# GroundStationCR.net
KiCad netlist of a schematic drawn in EAGLE
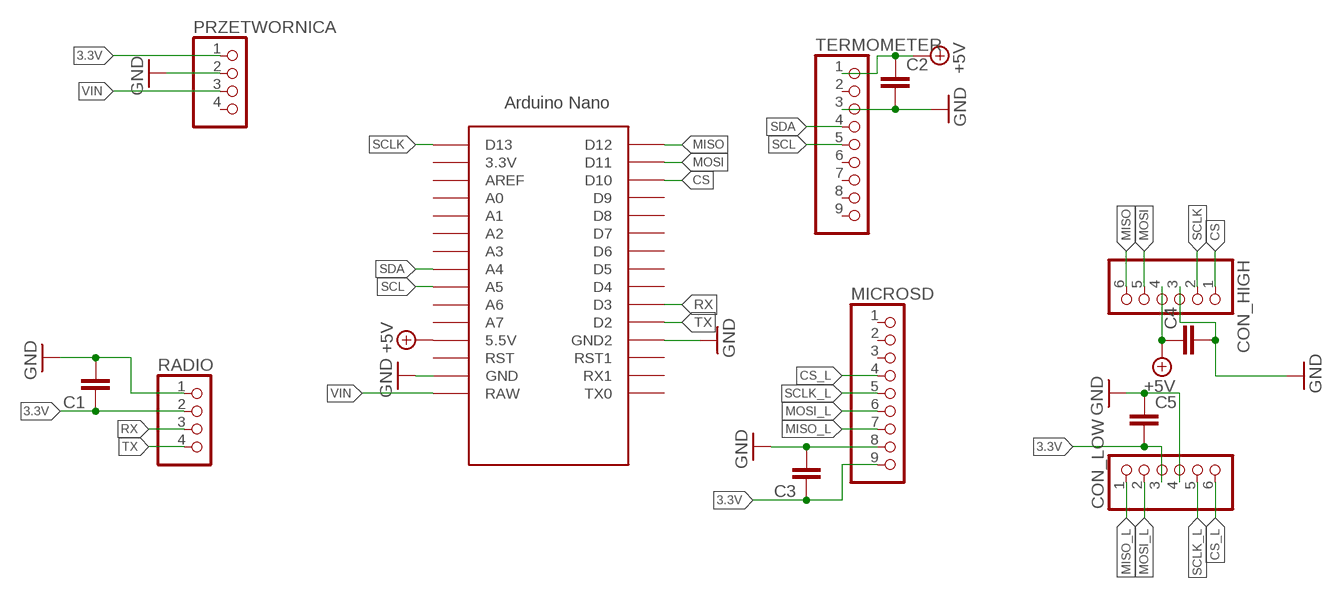
[diagram p0: schematic, sheet 1]

(export (version "E")
  (design (tool "Eeschema 10.0.6"))
  (components
    (comp (ref "C1")
      (value "C-EU050-025X075")
      (footprint "eagle-import:C050-025X075")
      (libsource (lib "eagle-import") (part "C-EU050-025X075"))
    )
    (comp (ref "C2")
      (value "C-EU050-025X075")
      (footprint "eagle-import:C050-025X075")
      (libsource (lib "eagle-import") (part "C-EU050-025X075"))
    )
    (comp (ref "C3")
      (value "C-EU050-025X075")
      (footprint "eagle-import:C050-025X075")
      (libsource (lib "eagle-import") (part "C-EU050-025X075"))
    )
    (comp (ref "C4")
      (value "C-EU050-025X075")
      (footprint "eagle-import:C050-025X075")
      (libsource (lib "eagle-import") (part "C-EU050-025X075"))
    )
    (comp (ref "C5")
      (value "C-EU050-025X075")
      (footprint "eagle-import:C050-025X075")
      (libsource (lib "eagle-import") (part "C-EU050-025X075"))
    )
    (comp (ref "CON_HIGH")
      (value "PINHD-1X6")
      (footprint "eagle-import:1X06")
      (libsource (lib "eagle-import") (part "PINHD-1X6"))
    )
    (comp (ref "CON_LOW")
      (value "PINHD-1X6")
      (footprint "eagle-import:1X06")
      (libsource (lib "eagle-import") (part "PINHD-1X6"))
    )
    (comp (ref "MICROSD")
      (value "PINHD-1X9")
      (footprint "eagle-import:1X09")
      (libsource (lib "eagle-import") (part "PINHD-1X9"))
    )
    (comp (ref "PRZETWORNICA")
      (value "PINHD-1X4")
      (footprint "eagle-import:1X04")
      (libsource (lib "eagle-import") (part "PINHD-1X4"))
    )
    (comp (ref "RADIO")
      (value "PINHD-1X4")
      (footprint "eagle-import:1X04")
      (libsource (lib "eagle-import") (part "PINHD-1X4"))
    )
    (comp (ref "TERMOMETER")
      (value "PINHD-1X9")
      (footprint "eagle-import:1X09")
      (libsource (lib "eagle-import") (part "PINHD-1X9"))
    )
    (comp (ref "U$1")
      (value "NANO")
      (footprint "eagle-import:NANO")
      (libsource (lib "eagle-import") (part "NANO"))
    )
  )
  (nets
    (net (code "1") (name "+5V") (class "Default")
      (node (ref "C2") (pin "1") (pinfunction "1_1") (pintype "passive"))
      (node (ref "C4") (pin "1") (pinfunction "1_1") (pintype "passive"))
      (node (ref "CON_HIGH") (pin "4") (pinfunction "4_4") (pintype "passive"))
      (node (ref "TERMOMETER") (pin "1") (pinfunction "1_1") (pintype "passive"))
      (node (ref "U$1") (pin "5V") (pinfunction "5.5V_5V") (pintype "bidirectional"))
    )
    (net (code "2") (name "3.3V") (class "Default")
      (node (ref "C1") (pin "1") (pinfunction "1_1") (pintype "passive"))
      (node (ref "C3") (pin "1") (pinfunction "1_1") (pintype "passive"))
      (node (ref "C5") (pin "2") (pinfunction "2_2") (pintype "passive"))
      (node (ref "CON_LOW") (pin "3") (pinfunction "3_3") (pintype "passive"))
      (node (ref "MICROSD") (pin "9") (pinfunction "9_9") (pintype "passive"))
      (node (ref "PRZETWORNICA") (pin "1") (pinfunction "1_1") (pintype "passive"))
      (node (ref "RADIO") (pin "2") (pinfunction "2_2") (pintype "passive"))
    )
    (net (code "3") (name "CS") (class "Default")
      (node (ref "CON_HIGH") (pin "1") (pinfunction "1_1") (pintype "passive"))
      (node (ref "U$1") (pin "D10") (pinfunction "D10_D10") (pintype "bidirectional"))
    )
    (net (code "4") (name "CS_L") (class "Default")
      (node (ref "CON_LOW") (pin "6") (pinfunction "6_6") (pintype "passive"))
      (node (ref "MICROSD") (pin "4") (pinfunction "4_4") (pintype "passive"))
    )
    (net (code "5") (name "GND") (class "Default")
      (node (ref "C1") (pin "2") (pinfunction "2_2") (pintype "passive"))
      (node (ref "C2") (pin "2") (pinfunction "2_2") (pintype "passive"))
      (node (ref "C3") (pin "2") (pinfunction "2_2") (pintype "passive"))
      (node (ref "C4") (pin "2") (pinfunction "2_2") (pintype "passive"))
      (node (ref "C5") (pin "1") (pinfunction "1_1") (pintype "passive"))
      (node (ref "CON_HIGH") (pin "3") (pinfunction "3_3") (pintype "passive"))
      (node (ref "CON_LOW") (pin "4") (pinfunction "4_4") (pintype "passive"))
      (node (ref "MICROSD") (pin "8") (pinfunction "8_8") (pintype "passive"))
      (node (ref "PRZETWORNICA") (pin "2") (pinfunction "2_2") (pintype "passive"))
      (node (ref "RADIO") (pin "1") (pinfunction "1_1") (pintype "passive"))
      (node (ref "TERMOMETER") (pin "3") (pinfunction "3_3") (pintype "passive"))
      (node (ref "U$1") (pin "GND") (pinfunction "GND_GND") (pintype "bidirectional"))
      (node (ref "U$1") (pin "GND1") (pinfunction "GND2_GND1") (pintype "bidirectional"))
    )
    (net (code "6") (name "MISO") (class "Default")
      (node (ref "CON_HIGH") (pin "6") (pinfunction "6_6") (pintype "passive"))
      (node (ref "U$1") (pin "D12") (pinfunction "D12_D12") (pintype "bidirectional"))
    )
    (net (code "7") (name "MISO_L") (class "Default")
      (node (ref "CON_LOW") (pin "1") (pinfunction "1_1") (pintype "passive"))
      (node (ref "MICROSD") (pin "7") (pinfunction "7_7") (pintype "passive"))
    )
    (net (code "8") (name "MOSI") (class "Default")
      (node (ref "CON_HIGH") (pin "5") (pinfunction "5_5") (pintype "passive"))
      (node (ref "U$1") (pin "D11") (pinfunction "D11_D11") (pintype "bidirectional"))
    )
    (net (code "9") (name "MOSI_L") (class "Default")
      (node (ref "CON_LOW") (pin "2") (pinfunction "2_2") (pintype "passive"))
      (node (ref "MICROSD") (pin "6") (pinfunction "6_6") (pintype "passive"))
    )
    (net (code "10") (name "RX") (class "Default")
      (node (ref "RADIO") (pin "3") (pinfunction "3_3") (pintype "passive"))
      (node (ref "U$1") (pin "D3") (pinfunction "D3_D3") (pintype "bidirectional"))
    )
    (net (code "11") (name "SCL") (class "Default")
      (node (ref "TERMOMETER") (pin "5") (pinfunction "5_5") (pintype "passive"))
      (node (ref "U$1") (pin "A5") (pinfunction "A5_A5") (pintype "bidirectional"))
    )
    (net (code "12") (name "SCLK") (class "Default")
      (node (ref "CON_HIGH") (pin "2") (pinfunction "2_2") (pintype "passive"))
      (node (ref "U$1") (pin "D13") (pinfunction "D13_D13") (pintype "bidirectional"))
    )
    (net (code "13") (name "SCLK_L") (class "Default")
      (node (ref "CON_LOW") (pin "5") (pinfunction "5_5") (pintype "passive"))
      (node (ref "MICROSD") (pin "5") (pinfunction "5_5") (pintype "passive"))
    )
    (net (code "14") (name "SDA") (class "Default")
      (node (ref "TERMOMETER") (pin "4") (pinfunction "4_4") (pintype "passive"))
      (node (ref "U$1") (pin "A4") (pinfunction "A4_A4") (pintype "bidirectional"))
    )
    (net (code "15") (name "TX") (class "Default")
      (node (ref "RADIO") (pin "4") (pinfunction "4_4") (pintype "passive"))
      (node (ref "U$1") (pin "D2") (pinfunction "D2_D2") (pintype "bidirectional"))
    )
    (net (code "16") (name "VIN") (class "Default")
      (node (ref "PRZETWORNICA") (pin "3") (pinfunction "3_3") (pintype "passive"))
      (node (ref "U$1") (pin "RAW") (pinfunction "RAW_RAW") (pintype "bidirectional"))
    )
    (net (code "17") (name "unconnected-(MICROSD-Pad1)") (class "Default")
      (node (ref "MICROSD") (pin "1") (pinfunction "1_1") (pintype "passive"))
    )
    (net (code "18") (name "unconnected-(MICROSD-Pad2)") (class "Default")
      (node (ref "MICROSD") (pin "2") (pinfunction "2_2") (pintype "passive"))
    )
    (net (code "19") (name "unconnected-(MICROSD-Pad3)") (class "Default")
      (node (ref "MICROSD") (pin "3") (pinfunction "3_3") (pintype "passive"))
    )
    (net (code "20") (name "unconnected-(PRZETWORNICA-Pad4)") (class "Default")
      (node (ref "PRZETWORNICA") (pin "4") (pinfunction "4_4") (pintype "passive"))
    )
    (net (code "21") (name "unconnected-(TERMOMETER-Pad2)") (class "Default")
      (node (ref "TERMOMETER") (pin "2") (pinfunction "2_2") (pintype "passive"))
    )
    (net (code "22") (name "unconnected-(TERMOMETER-Pad6)") (class "Default")
      (node (ref "TERMOMETER") (pin "6") (pinfunction "6_6") (pintype "passive"))
    )
    (net (code "23") (name "unconnected-(TERMOMETER-Pad7)") (class "Default")
      (node (ref "TERMOMETER") (pin "7") (pinfunction "7_7") (pintype "passive"))
    )
    (net (code "24") (name "unconnected-(TERMOMETER-Pad8)") (class "Default")
      (node (ref "TERMOMETER") (pin "8") (pinfunction "8_8") (pintype "passive"))
    )
    (net (code "25") (name "unconnected-(TERMOMETER-Pad9)") (class "Default")
      (node (ref "TERMOMETER") (pin "9") (pinfunction "9_9") (pintype "passive"))
    )
    (net (code "26") (name "unconnected-(U$1-Pad3.3V)") (class "Default")
      (node (ref "U$1") (pin "3.3V") (pinfunction "3.3V_3.3V") (pintype "bidirectional"))
    )
    (net (code "27") (name "unconnected-(U$1-PadA0)") (class "Default")
      (node (ref "U$1") (pin "A0") (pinfunction "A0_A0") (pintype "bidirectional"))
    )
    (net (code "28") (name "unconnected-(U$1-PadA1)") (class "Default")
      (node (ref "U$1") (pin "A1") (pinfunction "A1_A1") (pintype "bidirectional"))
    )
    (net (code "29") (name "unconnected-(U$1-PadA2)") (class "Default")
      (node (ref "U$1") (pin "A2") (pinfunction "A2_A2") (pintype "bidirectional"))
    )
    (net (code "30") (name "unconnected-(U$1-PadA3)") (class "Default")
      (node (ref "U$1") (pin "A3") (pinfunction "A3_A3") (pintype "bidirectional"))
    )
    (net (code "31") (name "unconnected-(U$1-PadA6)") (class "Default")
      (node (ref "U$1") (pin "A6") (pinfunction "A6_A6") (pintype "bidirectional"))
    )
    (net (code "32") (name "unconnected-(U$1-PadA7)") (class "Default")
      (node (ref "U$1") (pin "A7") (pinfunction "A7_A7") (pintype "bidirectional"))
    )
    (net (code "33") (name "unconnected-(U$1-PadAREF)") (class "Default")
      (node (ref "U$1") (pin "AREF") (pinfunction "AREF_AREF") (pintype "bidirectional"))
    )
    (net (code "34") (name "unconnected-(U$1-PadD4)") (class "Default")
      (node (ref "U$1") (pin "D4") (pinfunction "D4_D4") (pintype "bidirectional"))
    )
    (net (code "35") (name "unconnected-(U$1-PadD5)") (class "Default")
      (node (ref "U$1") (pin "D5") (pinfunction "D5_D5") (pintype "bidirectional"))
    )
    (net (code "36") (name "unconnected-(U$1-PadD6)") (class "Default")
      (node (ref "U$1") (pin "D6") (pinfunction "D6_D6") (pintype "bidirectional"))
    )
    (net (code "37") (name "unconnected-(U$1-PadD7)") (class "Default")
      (node (ref "U$1") (pin "D7") (pinfunction "D7_D7") (pintype "bidirectional"))
    )
    (net (code "38") (name "unconnected-(U$1-PadD8)") (class "Default")
      (node (ref "U$1") (pin "D8") (pinfunction "D8_D8") (pintype "bidirectional"))
    )
    (net (code "39") (name "unconnected-(U$1-PadD9)") (class "Default")
      (node (ref "U$1") (pin "D9") (pinfunction "D9_D9") (pintype "bidirectional"))
    )
    (net (code "40") (name "unconnected-(U$1-PadICSP1)") (class "Default")
      (node (ref "U$1") (pin "ICSP1") (pinfunction "ICSP1_ICSP1") (pintype "bidirectional"))
    )
    (net (code "41") (name "unconnected-(U$1-PadICSP2)") (class "Default")
      (node (ref "U$1") (pin "ICSP2") (pinfunction "ICSP2_ICSP2") (pintype "bidirectional"))
    )
    (net (code "42") (name "unconnected-(U$1-PadICSP3)") (class "Default")
      (node (ref "U$1") (pin "ICSP3") (pinfunction "ICSP3_ICSP3") (pintype "bidirectional"))
    )
    (net (code "43") (name "unconnected-(U$1-PadICSP4)") (class "Default")
      (node (ref "U$1") (pin "ICSP4") (pinfunction "ICSP4_ICSP4") (pintype "bidirectional"))
    )
    (net (code "44") (name "unconnected-(U$1-PadICSP5)") (class "Default")
      (node (ref "U$1") (pin "ICSP5") (pinfunction "ICSP5_ICSP5") (pintype "bidirectional"))
    )
    (net (code "45") (name "unconnected-(U$1-PadICSP6)") (class "Default")
      (node (ref "U$1") (pin "ICSP6") (pinfunction "ICSP6_ICSP6") (pintype "bidirectional"))
    )
    (net (code "46") (name "unconnected-(U$1-PadRST)") (class "Default")
      (node (ref "U$1") (pin "RST") (pinfunction "RST_RST") (pintype "bidirectional"))
    )
    (net (code "47") (name "unconnected-(U$1-PadRST1)") (class "Default")
      (node (ref "U$1") (pin "RST1") (pinfunction "RST1_RST1") (pintype "bidirectional"))
    )
    (net (code "48") (name "unconnected-(U$1-PadRX1)") (class "Default")
      (node (ref "U$1") (pin "RX1") (pinfunction "RX1_RX1") (pintype "bidirectional"))
    )
    (net (code "49") (name "unconnected-(U$1-PadTX0)") (class "Default")
      (node (ref "U$1") (pin "TX0") (pinfunction "TX0_TX0") (pintype "bidirectional"))
    )
  )
)
